# Sheet1.net
KiCad netlist of a schematic drawn in Altium Designer
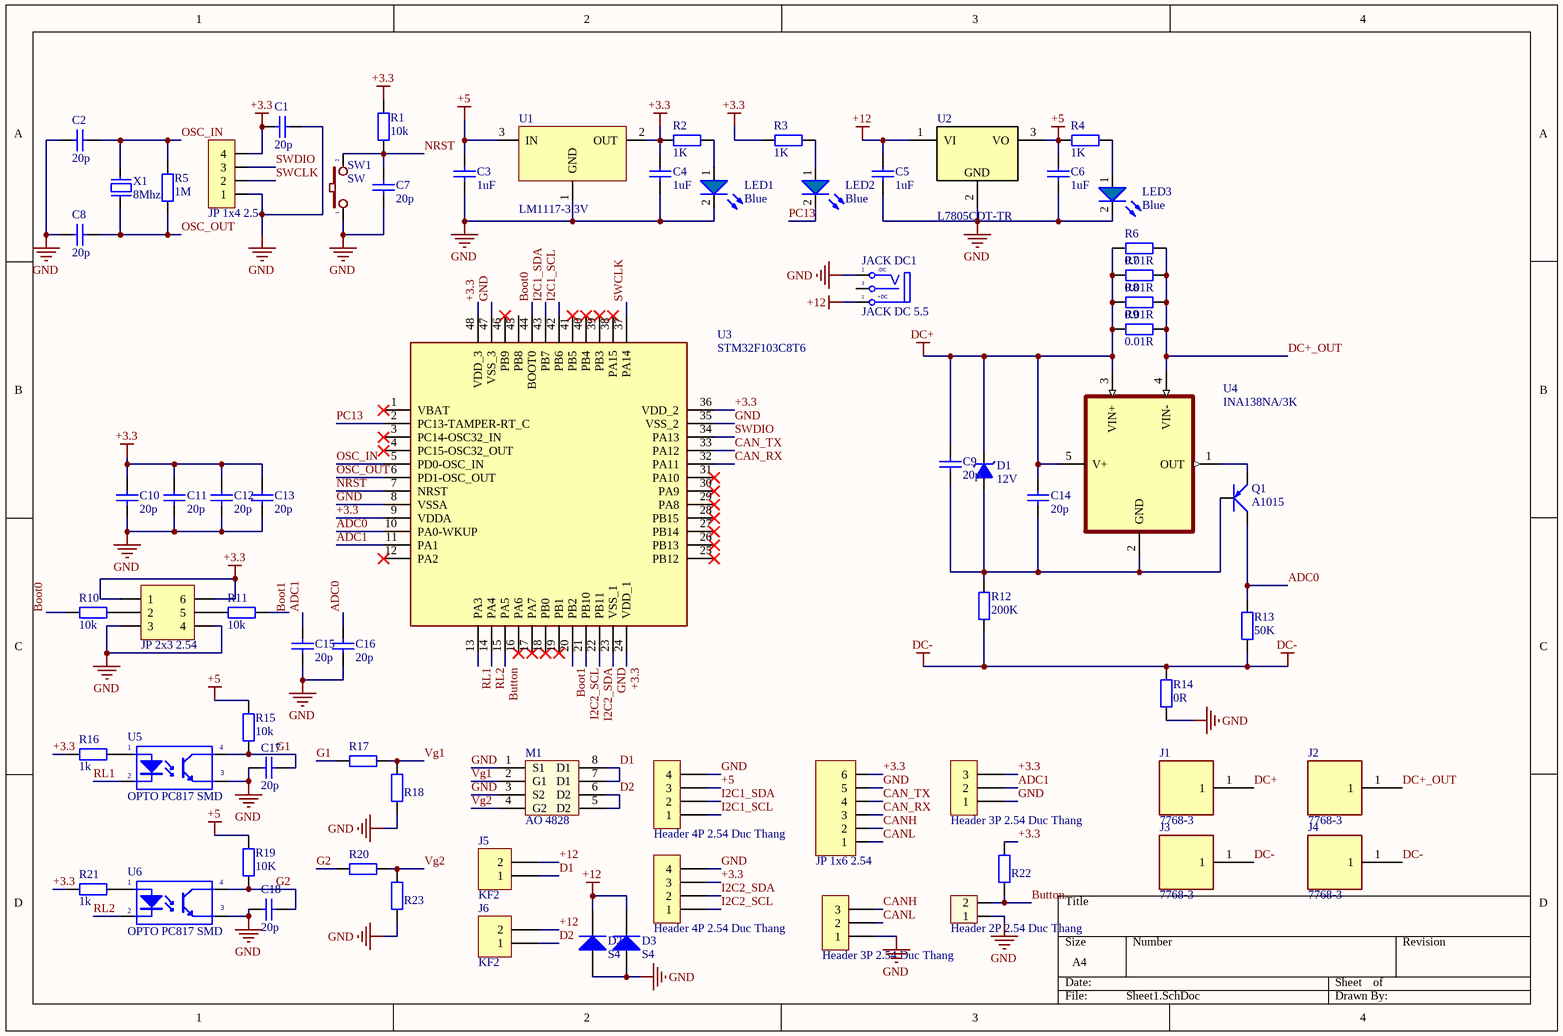
[diagram p0: Sheet1.SchDoc]

(export (version "E")
  (design (tool "Eeschema 10.0.6"))
  (components
    (comp (ref "C1")
      (value "20p")
      (footprint "tu 0805")
      (description "Dán")
      (libsource (lib "Altium_Lib_by_KhueNguyenCreator") (part "Tu 0805 474 50V 10%"))
    )
    (comp (ref "C2")
      (value "20p")
      (footprint "tu 0805")
      (description "Dán")
      (libsource (lib "Altium_Lib_by_KhueNguyenCreator") (part "Tu 0805 474 50V 10%"))
    )
    (comp (ref "C3")
      (value "1uF")
      (footprint "tu 0805")
      (description "Dán")
      (libsource (lib "Altium_Lib_by_KhueNguyenCreator") (part "Tu 0805 474 50V 10%"))
    )
    (comp (ref "C4")
      (value "1uF")
      (footprint "tu 0805")
      (description "Dán")
      (libsource (lib "Altium_Lib_by_KhueNguyenCreator") (part "Tu 0805 474 50V 10%"))
    )
    (comp (ref "C5")
      (value "1uF")
      (footprint "tu 0805")
      (description "Dán")
      (libsource (lib "Altium_Lib_by_KhueNguyenCreator") (part "Tu 0805 474 50V 10%"))
    )
    (comp (ref "C6")
      (value "1uF")
      (footprint "tu 0805")
      (description "Dán")
      (libsource (lib "Altium_Lib_by_KhueNguyenCreator") (part "Tu 0805 474 50V 10%"))
    )
    (comp (ref "C7")
      (value "20p")
      (footprint "tu 0805")
      (description "Dán")
      (libsource (lib "Altium_Lib_by_KhueNguyenCreator") (part "Tu 0805 474 50V 10%"))
    )
    (comp (ref "C8")
      (value "20p")
      (footprint "tu 0805")
      (description "Dán")
      (libsource (lib "Altium_Lib_by_KhueNguyenCreator") (part "Tu 0805 474 50V 10%"))
    )
    (comp (ref "C9")
      (value "20p")
      (footprint "tu 0805")
      (description "Dán")
      (libsource (lib "Altium_Lib_by_KhueNguyenCreator") (part "Tu 0805 474 50V 10%"))
    )
    (comp (ref "C10")
      (value "20p")
      (footprint "tu 0805")
      (description "Dán")
      (libsource (lib "Altium_Lib_by_KhueNguyenCreator") (part "Tu 0805 474 50V 10%"))
    )
    (comp (ref "C11")
      (value "20p")
      (footprint "tu 0805")
      (description "Dán")
      (libsource (lib "Altium_Lib_by_KhueNguyenCreator") (part "Tu 0805 474 50V 10%"))
    )
    (comp (ref "C12")
      (value "20p")
      (footprint "tu 0805")
      (description "Dán")
      (libsource (lib "Altium_Lib_by_KhueNguyenCreator") (part "Tu 0805 474 50V 10%"))
    )
    (comp (ref "C13")
      (value "20p")
      (footprint "tu 0805")
      (description "Dán")
      (libsource (lib "Altium_Lib_by_KhueNguyenCreator") (part "Tu 0805 474 50V 10%"))
    )
    (comp (ref "C14")
      (value "20p")
      (footprint "tu 0805")
      (description "Dán")
      (libsource (lib "Altium_Lib_by_KhueNguyenCreator") (part "Tu 0805 474 50V 10%"))
    )
    (comp (ref "C15")
      (value "20p")
      (footprint "tu 0805")
      (description "Dán")
      (libsource (lib "Altium_Lib_by_KhueNguyenCreator") (part "Tu 0805 474 50V 10%"))
    )
    (comp (ref "C16")
      (value "20p")
      (footprint "tu 0805")
      (description "Dán")
      (libsource (lib "Altium_Lib_by_KhueNguyenCreator") (part "Tu 0805 474 50V 10%"))
    )
    (comp (ref "C17")
      (value "20p")
      (footprint "tu 0805")
      (description "Dán")
      (libsource (lib "Altium_Lib_by_KhueNguyenCreator") (part "Tu 0805 474 50V 10%"))
    )
    (comp (ref "C18")
      (value "20p")
      (footprint "tu 0805")
      (description "Dán")
      (libsource (lib "Altium_Lib_by_KhueNguyenCreator") (part "Tu 0805 474 50V 10%"))
    )
    (comp (ref "D1")
      (value "12V")
      (footprint "DIODE ZENNER SMD SOD80")
      (description "Dán")
      (libsource (lib "Altium_Lib_by_KhueNguyenCreator") (part "Diode Zener 12V"))
    )
    (comp (ref "D2")
      (value "S4")
      (footprint "DIODE SOD-123")
      (description "Dán")
      (libsource (lib "Altium_Lib_by_KhueNguyenCreator") (part "Diode S4"))
    )
    (comp (ref "D3")
      (value "S4")
      (footprint "DIODE SOD-123")
      (description "Dán")
      (libsource (lib "Altium_Lib_by_KhueNguyenCreator") (part "Diode S4"))
    )
    (comp (ref "H1")
      (value "Header 4P 2.54 Duc Thang")
      (footprint "XH2.54M-4")
      (description "Cắm")
      (libsource (lib "Altium_Lib_by_KhueNguyenCreator") (part "Header 4P 2.54 Duc Thang"))
    )
    (comp (ref "H2")
      (value "Header 3P 2.54 Duc Thang")
      (footprint "XH2.54M-3")
      (description "Cắm")
      (libsource (lib "Altium_Lib_by_KhueNguyenCreator") (part "Header 3P 2.54 Duc Thang"))
    )
    (comp (ref "H3")
      (value "Header 4P 2.54 Duc Thang")
      (footprint "XH2.54M-4")
      (description "Cắm")
      (libsource (lib "Altium_Lib_by_KhueNguyenCreator") (part "Header 4P 2.54 Duc Thang"))
    )
    (comp (ref "H4")
      (value "Header 3P 2.54 Duc Thang")
      (footprint "XH2.54M-3")
      (description "Cắm")
      (libsource (lib "Altium_Lib_by_KhueNguyenCreator") (part "Header 3P 2.54 Duc Thang"))
    )
    (comp (ref "H5")
      (value "Header 2P 2.54 Duc Thang")
      (footprint "XH2.54M-2")
      (description "Cắm")
      (libsource (lib "Altium_Lib_by_KhueNguyenCreator") (part "Header 2P 2.54 Duc Thang"))
    )
    (comp (ref "J1")
      (value "7768-3")
      (footprint "KEYSTONE_7768-3")
      (libsource (lib "7768-3") (part "7768-3"))
    )
    (comp (ref "J2")
      (value "7768-3")
      (footprint "KEYSTONE_7768-3")
      (libsource (lib "7768-3") (part "7768-3"))
    )
    (comp (ref "J3")
      (value "7768-3")
      (footprint "KEYSTONE_7768-3")
      (libsource (lib "7768-3") (part "7768-3"))
    )
    (comp (ref "J4")
      (value "7768-3")
      (footprint "KEYSTONE_7768-3")
      (libsource (lib "7768-3") (part "7768-3"))
    )
    (comp (ref "J5")
      (value "KF2")
      (footprint "KF2-5.08")
      (fields
        (field (name "MANUFACTURER") "Würth Elektronik eiSos GmbH")
        (field (name "PARTNO") "691103110002")
        (field (name "CREATED BY") "Karrer Zheng")
      )
      (libsource (lib "TechMT.VN_Lib_Project v2") (part "KF2"))
    )
    (comp (ref "J6")
      (value "KF2")
      (footprint "KF2-5.08")
      (fields
        (field (name "MANUFACTURER") "Würth Elektronik eiSos GmbH")
        (field (name "PARTNO") "691103110002")
        (field (name "CREATED BY") "Karrer Zheng")
      )
      (libsource (lib "TechMT.VN_Lib_Project v2") (part "KF2"))
    )
    (comp (ref "JACK DC1")
      (value "JACK DC 5.5")
      (footprint "JACK DC 5.5")
      (libsource (lib "Altium_Lib_by_KhueNguyenCreator") (part "JACK DC 5.5"))
    )
    (comp (ref "JP1")
      (value "JP 1x4 2.54")
      (footprint "JP 1x4 DT")
      (description "Cắm")
      (libsource (lib "Altium_Lib_by_KhueNguyenCreator") (part "JP 1x4 2.54 Duc Thang"))
    )
    (comp (ref "JP2")
      (value "JP 2x3 2.54")
      (footprint "JP 2x3 DT")
      (description "Cắm")
      (libsource (lib "Altium_Lib_by_KhueNguyenCreator") (part "JP 2x3 2.54 Duc Thang"))
    )
    (comp (ref "JP3")
      (value "JP 1x6 2.54")
      (footprint "JP 1x6 CT")
      (description "Cắm")
      (libsource (lib "Altium_Lib_by_KhueNguyenCreator") (part "JP 1x6 2.54 Cai Thang"))
    )
    (comp (ref "LED1")
      (value "Blue")
      (footprint "LED-0805-Blue")
      (description "LED Blue 10mA 2.2v")
      (fields (field (name "Comment") "LED-Blue"))
      (libsource (lib "TechMT.VN_Lib_Project v2") (part "LED-Blue"))
    )
    (comp (ref "LED2")
      (value "Blue")
      (footprint "LED-0805-Blue")
      (description "LED Blue 10mA 2.2v")
      (fields (field (name "Comment") "LED-Blue"))
      (libsource (lib "TechMT.VN_Lib_Project v2") (part "LED-Blue"))
    )
    (comp (ref "LED3")
      (value "Blue")
      (footprint "LED-0805-Blue")
      (description "LED Blue 10mA 2.2v")
      (fields (field (name "Comment") "LED-Blue"))
      (libsource (lib "TechMT.VN_Lib_Project v2") (part "LED-Blue"))
    )
    (comp (ref "M1")
      (value "AO 4828")
      (footprint "SOp 8")
      (description "Dán")
      (libsource (lib "Altium_Lib_by_KhueNguyenCreator") (part "APM 4828 SMD"))
    )
    (comp (ref "Q1")
      (value "A1015")
      (footprint "TO92")
      (description "PNP 600mW, ECB")
      (libsource (lib "Altium_Lib_by_KhueNguyenCreator") (part "A1015"))
    )
    (comp (ref "R1")
      (value "10k")
      (footprint "tro smd 0805")
      (description "Dán")
      (libsource (lib "Altium_Lib_by_KhueNguyenCreator") (part "Tro 0805 1% 33k"))
    )
    (comp (ref "R2")
      (value "1K")
      (footprint "tro smd 0805")
      (description "Dán")
      (libsource (lib "Altium_Lib_by_KhueNguyenCreator") (part "Tro 0805 1% 33k"))
    )
    (comp (ref "R3")
      (value "1K")
      (footprint "tro smd 0805")
      (description "Dán")
      (libsource (lib "Altium_Lib_by_KhueNguyenCreator") (part "Tro 0805 1% 33k"))
    )
    (comp (ref "R4")
      (value "1K")
      (footprint "tro smd 0805")
      (description "Dán")
      (libsource (lib "Altium_Lib_by_KhueNguyenCreator") (part "Tro 0805 1% 33k"))
    )
    (comp (ref "R5")
      (value "1M")
      (footprint "tro smd 0805")
      (description "Dán")
      (libsource (lib "Altium_Lib_by_KhueNguyenCreator") (part "Tro 0805 1% 33k"))
    )
    (comp (ref "R6")
      (value "0.01R")
      (footprint "tro smd 2512")
      (description "Dán")
      (libsource (lib "Altium_Lib_by_KhueNguyenCreator") (part "Tro 2512 1% 0.01R"))
    )
    (comp (ref "R7")
      (value "0.01R")
      (footprint "tro smd 2512")
      (description "Dán")
      (libsource (lib "Altium_Lib_by_KhueNguyenCreator") (part "Tro 2512 1% 0.01R"))
    )
    (comp (ref "R8")
      (value "0.01R")
      (footprint "tro smd 2512")
      (description "Dán")
      (libsource (lib "Altium_Lib_by_KhueNguyenCreator") (part "Tro 2512 1% 0.01R"))
    )
    (comp (ref "R9")
      (value "0.01R")
      (footprint "tro smd 2512")
      (description "Dán")
      (libsource (lib "Altium_Lib_by_KhueNguyenCreator") (part "Tro 2512 1% 0.01R"))
    )
    (comp (ref "R10")
      (value "10k")
      (footprint "tro smd 0805")
      (description "Dán")
      (libsource (lib "Altium_Lib_by_KhueNguyenCreator") (part "Tro 0805 1% 33k"))
    )
    (comp (ref "R11")
      (value "10k")
      (footprint "tro smd 0805")
      (description "Dán")
      (libsource (lib "Altium_Lib_by_KhueNguyenCreator") (part "Tro 0805 1% 33k"))
    )
    (comp (ref "R12")
      (value "200K")
      (footprint "tro vach 1/4w")
      (description "Cắm")
      (libsource (lib "Altium_Lib_by_KhueNguyenCreator") (part "Tro Vach 1/4W 5% 1.2M"))
    )
    (comp (ref "R13")
      (value "50K")
      (footprint "tro smd 0805")
      (description "Dán")
      (libsource (lib "Altium_Lib_by_KhueNguyenCreator") (part "Tro 0805 1% 33k"))
    )
    (comp (ref "R14")
      (value "0R")
      (footprint "tro smd 0805")
      (description "Dán")
      (libsource (lib "Altium_Lib_by_KhueNguyenCreator") (part "Tro 0805 1% 33k"))
    )
    (comp (ref "R15")
      (value "10k")
      (footprint "tro smd 0805")
      (description "Dán")
      (libsource (lib "Altium_Lib_by_KhueNguyenCreator") (part "Tro 0805 1% 33k"))
    )
    (comp (ref "R16")
      (value "1k")
      (footprint "tro smd 0805")
      (description "Dán")
      (libsource (lib "Altium_Lib_by_KhueNguyenCreator") (part "Tro 0805 1% 33k"))
    )
    (comp (ref "R17")
      (value "1k")
      (footprint "tro smd 0805")
      (description "Dán")
      (libsource (lib "Altium_Lib_by_KhueNguyenCreator") (part "Tro 0805 1% 33k"))
    )
    (comp (ref "R18")
      (value "10k")
      (footprint "tro smd 0805")
      (description "Dán")
      (libsource (lib "Altium_Lib_by_KhueNguyenCreator") (part "Tro 0805 1% 33k"))
    )
    (comp (ref "R19")
      (value "10K")
      (footprint "tro smd 0805")
      (description "Dán")
      (libsource (lib "Altium_Lib_by_KhueNguyenCreator") (part "Tro 0805 1% 33k"))
    )
    (comp (ref "R20")
      (value "1k")
      (footprint "tro smd 0805")
      (description "Dán")
      (libsource (lib "Altium_Lib_by_KhueNguyenCreator") (part "Tro 0805 1% 33k"))
    )
    (comp (ref "R21")
      (value "1k")
      (footprint "tro smd 0805")
      (description "Dán")
      (libsource (lib "Altium_Lib_by_KhueNguyenCreator") (part "Tro 0805 1% 33k"))
    )
    (comp (ref "R22")
      (value "10k")
      (footprint "tro smd 0805")
      (description "Dán")
      (libsource (lib "Altium_Lib_by_KhueNguyenCreator") (part "Tro 0805 1% 33k"))
    )
    (comp (ref "R23")
      (value "10k")
      (footprint "tro smd 0805")
      (description "Dán")
      (libsource (lib "Altium_Lib_by_KhueNguyenCreator") (part "Tro 0805 1% 33k"))
    )
    (comp (ref "SW1")
      (value "SW")
      (footprint "SW1-SMD")
      (description "Switch button 2 pin")
      (libsource (lib "TechMT.VN_Lib_Project v2") (part "SW2"))
    )
    (comp (ref "U1")
      (value "LM1117-3.3V")
      (footprint "SOT223")
      (description "800mA Low-Dropout Linear Regulator")
      (fields (field (name "CREATOR") "Nguyen Ba Bien"))
      (libsource (lib "TechMT.VN_Lib_Project v2") (part "LM1117"))
    )
    (comp (ref "U2")
      (value "L7805CDT-TR")
      (footprint "DPAK_118_446_112X59_SMD")
      (description "Linear Voltage Regulator IC 1 Output 1.5A DPAK")
      (fields (field (name "MANUFACTURER") "Diodes"))
      (libsource (lib "Altium_Lib_by_KhueNguyenCreator") (part "REG_35V_5V-1.5A-7.5W-DPAK"))
    )
    (comp (ref "U3")
      (value "STM32F103C8T6")
      (footprint "LQFP-48_19.6_393_58X11_SMD")
      (description "ARM® Cortex®-M3 STM32F1 Microcontroller IC 32-Bit 72MHz 64KB (64K x 8) FLASH 48-LQFP (7x7)")
      (fields (field (name "MANUFACTURER") "STMicroelectronics"))
      (libsource (lib "Altium_Lib_by_KhueNguyenCreator") (part "IC_STM32F103C8T6"))
    )
    (comp (ref "U4")
      (value "INA138NA/3K")
      (footprint "SOT95P280X145-5N")
      (description "2.7 to 36V, 800kHz Variable gain current sense amplifier 5-SOT-23 -40 to 125")
      (fields (field (name "MF") "Texas Instruments"))
      (libsource (lib "INA138NA_3K") (part "INA138NA/3K"))
    )
    (comp (ref "U5")
      (value "OPTO PC817 SMD")
      (footprint "SOP4")
      (description "Single Opto")
      (libsource (lib "Altium_Lib_by_KhueNguyenCreator") (part "OPTO PC817 SMD"))
    )
    (comp (ref "U6")
      (value "OPTO PC817 SMD")
      (footprint "SOP4")
      (description "Single Opto")
      (libsource (lib "Altium_Lib_by_KhueNguyenCreator") (part "OPTO PC817 SMD"))
    )
    (comp (ref "X1")
      (value "8Mhz")
      (footprint "XT2")
      (description "Crystal, 32.768 KHz, -40 to 85 degC, 3.2 x 1.5 x 0.9 mm SMD")
      (libsource (lib "TechMT.VN_Lib_Project v2") (part "XT2"))
    )
  )
  (nets
    (net (code "1") (name "+3.3") (class "Default")
      (node (ref "C1") (pin "1") (pinfunction "1_1") (pintype "passive"))
      (node (ref "C10") (pin "1") (pinfunction "1_1") (pintype "passive"))
      (node (ref "C11") (pin "1") (pinfunction "1_1") (pintype "passive"))
      (node (ref "C12") (pin "1") (pinfunction "1_1") (pintype "passive"))
      (node (ref "C13") (pin "1") (pinfunction "1_1") (pintype "passive"))
      (node (ref "C4") (pin "1") (pinfunction "1_1") (pintype "passive"))
      (node (ref "H2") (pin "3") (pinfunction "3_3") (pintype "passive"))
      (node (ref "H3") (pin "3") (pinfunction "3_3") (pintype "passive"))
      (node (ref "JP1") (pin "4") (pinfunction "4_4") (pintype "passive"))
      (node (ref "JP2") (pin "1") (pinfunction "1_1") (pintype "passive"))
      (node (ref "JP2") (pin "6") (pinfunction "6_6") (pintype "passive"))
      (node (ref "JP3") (pin "6") (pinfunction "6_6") (pintype "passive"))
      (node (ref "R1") (pin "2") (pinfunction "2_2") (pintype "passive"))
      (node (ref "R16") (pin "1") (pinfunction "1_1") (pintype "passive"))
      (node (ref "R2") (pin "2") (pinfunction "2_2") (pintype "passive"))
      (node (ref "R21") (pin "1") (pinfunction "1_1") (pintype "passive"))
      (node (ref "R22") (pin "2") (pinfunction "2_2") (pintype "passive"))
      (node (ref "R3") (pin "2") (pinfunction "2_2") (pintype "passive"))
      (node (ref "U1") (pin "2") (pinfunction "OUT_2") (pintype "passive"))
      (node (ref "U3") (pin "24") (pinfunction "VDD_1_24") (pintype "passive"))
      (node (ref "U3") (pin "36") (pinfunction "VDD_2_36") (pintype "passive"))
      (node (ref "U3") (pin "48") (pinfunction "VDD_3_48") (pintype "passive"))
      (node (ref "U3") (pin "9") (pinfunction "VDDA_9") (pintype "passive"))
    )
    (net (code "2") (name "+5") (class "Default")
      (node (ref "C3") (pin "1") (pinfunction "1_1") (pintype "passive"))
      (node (ref "C6") (pin "1") (pinfunction "1_1") (pintype "passive"))
      (node (ref "H1") (pin "3") (pinfunction "3_3") (pintype "passive"))
      (node (ref "R15") (pin "1") (pinfunction "1_1") (pintype "passive"))
      (node (ref "R19") (pin "1") (pinfunction "1_1") (pintype "passive"))
      (node (ref "R4") (pin "2") (pinfunction "2_2") (pintype "passive"))
      (node (ref "U1") (pin "3") (pinfunction "IN_3") (pintype "passive"))
      (node (ref "U2") (pin "3") (pinfunction "VO_3") (pintype "passive"))
    )
    (net (code "3") (name "+12") (class "Default")
      (node (ref "C5") (pin "1") (pinfunction "1_1") (pintype "passive"))
      (node (ref "D2") (pin "2") (pinfunction "K_2") (pintype "passive"))
      (node (ref "D3") (pin "2") (pinfunction "K_2") (pintype "passive"))
      (node (ref "J5") (pin "2") (pinfunction "2_2") (pintype "passive"))
      (node (ref "J6") (pin "2") (pinfunction "2_2") (pintype "passive"))
      (node (ref "JACK DC1") (pin "1") (pinfunction "T_1") (pintype "passive"))
      (node (ref "U2") (pin "1") (pinfunction "VI_1") (pintype "passive"))
    )
    (net (code "4") (name "/ADC0") (class "Default")
      (node (ref "C16") (pin "2") (pinfunction "2_2") (pintype "passive"))
      (node (ref "Q1") (pin "2") (pinfunction "C_2") (pintype "passive"))
      (node (ref "R13") (pin "2") (pinfunction "2_2") (pintype "passive"))
      (node (ref "U3") (pin "10") (pinfunction "PA0-WKUP_10") (pintype "passive"))
    )
    (net (code "5") (name "/ADC1") (class "Default")
      (node (ref "C15") (pin "1") (pinfunction "1_1") (pintype "passive"))
      (node (ref "H2") (pin "2") (pinfunction "2_2") (pintype "passive"))
      (node (ref "U3") (pin "11") (pinfunction "PA1_11") (pintype "passive"))
    )
    (net (code "6") (name "/Boot0") (class "Default")
      (node (ref "R10") (pin "1") (pinfunction "1_1") (pintype "passive"))
      (node (ref "U3") (pin "44") (pinfunction "BOOT0_44") (pintype "passive"))
    )
    (net (code "7") (name "/Boot1") (class "Default")
      (node (ref "R11") (pin "2") (pinfunction "2_2") (pintype "passive"))
      (node (ref "U3") (pin "20") (pinfunction "PB2_20") (pintype "passive"))
    )
    (net (code "8") (name "/Button") (class "Default")
      (node (ref "H5") (pin "2") (pinfunction "2_2") (pintype "passive"))
      (node (ref "R22") (pin "1") (pinfunction "1_1") (pintype "passive"))
      (node (ref "U3") (pin "15") (pinfunction "PA5_15") (pintype "passive"))
    )
    (net (code "9") (name "/CANH") (class "Default")
      (node (ref "H4") (pin "3") (pinfunction "3_3") (pintype "passive"))
      (node (ref "JP3") (pin "2") (pinfunction "2_2") (pintype "passive"))
    )
    (net (code "10") (name "/CANL") (class "Default")
      (node (ref "H4") (pin "2") (pinfunction "2_2") (pintype "passive"))
      (node (ref "JP3") (pin "1") (pinfunction "1_1") (pintype "passive"))
    )
    (net (code "11") (name "/CAN_RX") (class "Default")
      (node (ref "JP3") (pin "3") (pinfunction "3_3") (pintype "passive"))
      (node (ref "U3") (pin "32") (pinfunction "PA11_32") (pintype "passive"))
    )
    (net (code "12") (name "/CAN_TX") (class "Default")
      (node (ref "JP3") (pin "4") (pinfunction "4_4") (pintype "passive"))
      (node (ref "U3") (pin "33") (pinfunction "PA12_33") (pintype "passive"))
    )
    (net (code "13") (name "/D1") (class "Default")
      (node (ref "J5") (pin "1") (pinfunction "1_1") (pintype "passive"))
      (node (ref "M1") (pin "7") (pinfunction "D1_7") (pintype "passive"))
      (node (ref "M1") (pin "8") (pinfunction "D1_8") (pintype "passive"))
    )
    (net (code "14") (name "/D2") (class "Default")
      (node (ref "J6") (pin "1") (pinfunction "1_1") (pintype "passive"))
      (node (ref "M1") (pin "5") (pinfunction "D2_5") (pintype "passive"))
      (node (ref "M1") (pin "6") (pinfunction "D2_6") (pintype "passive"))
    )
    (net (code "15") (name "/DC+_OUT") (class "Default")
      (node (ref "J2") (pin "1") (pinfunction "1_1") (pintype "passive"))
      (node (ref "R6") (pin "2") (pinfunction "2_2") (pintype "passive"))
      (node (ref "R7") (pin "2") (pinfunction "2_2") (pintype "passive"))
      (node (ref "R8") (pin "2") (pinfunction "2_2") (pintype "passive"))
      (node (ref "R9") (pin "2") (pinfunction "2_2") (pintype "passive"))
      (node (ref "U4") (pin "4") (pinfunction "VIN-_4") (pintype "input"))
    )
    (net (code "16") (name "/G1") (class "Default")
      (node (ref "C17") (pin "2") (pinfunction "2_2") (pintype "passive"))
      (node (ref "R15") (pin "2") (pinfunction "2_2") (pintype "passive"))
      (node (ref "R17") (pin "1") (pinfunction "1_1") (pintype "passive"))
      (node (ref "U5") (pin "4") (pinfunction "C_4") (pintype "passive"))
    )
    (net (code "17") (name "/G2") (class "Default")
      (node (ref "C18") (pin "2") (pinfunction "2_2") (pintype "passive"))
      (node (ref "R19") (pin "2") (pinfunction "2_2") (pintype "passive"))
      (node (ref "R20") (pin "1") (pinfunction "1_1") (pintype "passive"))
      (node (ref "U6") (pin "4") (pinfunction "C_4") (pintype "passive"))
    )
    (net (code "18") (name "/I2C1_SCL") (class "Default")
      (node (ref "H1") (pin "1") (pinfunction "1_1") (pintype "passive"))
      (node (ref "U3") (pin "42") (pinfunction "PB6_42") (pintype "passive"))
    )
    (net (code "19") (name "/I2C1_SDA") (class "Default")
      (node (ref "H1") (pin "2") (pinfunction "2_2") (pintype "passive"))
      (node (ref "U3") (pin "43") (pinfunction "PB7_43") (pintype "passive"))
    )
    (net (code "20") (name "/I2C2_SCL") (class "Default")
      (node (ref "H3") (pin "1") (pinfunction "1_1") (pintype "passive"))
      (node (ref "U3") (pin "21") (pinfunction "PB10_21") (pintype "passive"))
    )
    (net (code "21") (name "/I2C2_SDA") (class "Default")
      (node (ref "H3") (pin "2") (pinfunction "2_2") (pintype "passive"))
      (node (ref "U3") (pin "22") (pinfunction "PB11_22") (pintype "passive"))
    )
    (net (code "22") (name "/NRST") (class "Default")
      (node (ref "C7") (pin "1") (pinfunction "1_1") (pintype "passive"))
      (node (ref "R1") (pin "1") (pinfunction "1_1") (pintype "passive"))
      (node (ref "SW1") (pin "2") (pinfunction "2_2") (pintype "passive"))
      (node (ref "U3") (pin "7") (pinfunction "NRST_7") (pintype "passive"))
    )
    (net (code "23") (name "/OSC_IN") (class "Default")
      (node (ref "C2") (pin "1") (pinfunction "1_1") (pintype "passive"))
      (node (ref "R5") (pin "1") (pinfunction "1_1") (pintype "passive"))
      (node (ref "U3") (pin "5") (pinfunction "PD0-OSC_IN_5") (pintype "passive"))
      (node (ref "X1") (pin "2") (pinfunction "2_2") (pintype "passive"))
    )
    (net (code "24") (name "/OSC_OUT") (class "Default")
      (node (ref "C8") (pin "1") (pinfunction "1_1") (pintype "passive"))
      (node (ref "R5") (pin "2") (pinfunction "2_2") (pintype "passive"))
      (node (ref "U3") (pin "6") (pinfunction "PD1-OSC_OUT_6") (pintype "passive"))
      (node (ref "X1") (pin "1") (pinfunction "1_1") (pintype "passive"))
    )
    (net (code "25") (name "/PC13") (class "Default")
      (node (ref "LED2") (pin "2") (pinfunction "K_2") (pintype "passive"))
      (node (ref "U3") (pin "2") (pinfunction "PC13-TAMPER-RT_C_2") (pintype "passive"))
    )
    (net (code "26") (name "/RL1") (class "Default")
      (node (ref "U3") (pin "13") (pinfunction "PA3_13") (pintype "passive"))
      (node (ref "U5") (pin "2") (pinfunction "K_2") (pintype "passive"))
    )
    (net (code "27") (name "/RL2") (class "Default")
      (node (ref "U3") (pin "14") (pinfunction "PA4_14") (pintype "passive"))
      (node (ref "U6") (pin "2") (pinfunction "K_2") (pintype "passive"))
    )
    (net (code "28") (name "/SWCLK") (class "Default")
      (node (ref "JP1") (pin "2") (pinfunction "2_2") (pintype "passive"))
      (node (ref "U3") (pin "37") (pinfunction "PA14_37") (pintype "passive"))
    )
    (net (code "29") (name "/SWDIO") (class "Default")
      (node (ref "JP1") (pin "3") (pinfunction "3_3") (pintype "passive"))
      (node (ref "U3") (pin "34") (pinfunction "PA13_34") (pintype "passive"))
    )
    (net (code "30") (name "/Vg1") (class "Default")
      (node (ref "M1") (pin "2") (pinfunction "G1_2") (pintype "passive"))
      (node (ref "R17") (pin "2") (pinfunction "2_2") (pintype "passive"))
      (node (ref "R18") (pin "2") (pinfunction "2_2") (pintype "passive"))
    )
    (net (code "31") (name "/Vg2") (class "Default")
      (node (ref "M1") (pin "4") (pinfunction "G2_4") (pintype "passive"))
      (node (ref "R20") (pin "2") (pinfunction "2_2") (pintype "passive"))
      (node (ref "R23") (pin "2") (pinfunction "2_2") (pintype "passive"))
    )
    (net (code "32") (name "DC+") (class "Default")
      (node (ref "C14") (pin "1") (pinfunction "1_1") (pintype "passive"))
      (node (ref "C9") (pin "1") (pinfunction "1_1") (pintype "passive"))
      (node (ref "D1") (pin "2") (pinfunction "K_2") (pintype "passive"))
      (node (ref "J1") (pin "1") (pinfunction "1_1") (pintype "passive"))
      (node (ref "R6") (pin "1") (pinfunction "1_1") (pintype "passive"))
      (node (ref "R7") (pin "1") (pinfunction "1_1") (pintype "passive"))
      (node (ref "R8") (pin "1") (pinfunction "1_1") (pintype "passive"))
      (node (ref "R9") (pin "1") (pinfunction "1_1") (pintype "passive"))
      (node (ref "U4") (pin "3") (pinfunction "VIN+_3") (pintype "input"))
      (node (ref "U4") (pin "5") (pinfunction "V+_5") (pintype "power_in"))
    )
    (net (code "33") (name "DC-") (class "Default")
      (node (ref "J3") (pin "1") (pinfunction "1_1") (pintype "passive"))
      (node (ref "J4") (pin "1") (pinfunction "1_1") (pintype "passive"))
      (node (ref "R12") (pin "1") (pinfunction "1_1") (pintype "passive"))
      (node (ref "R13") (pin "1") (pinfunction "1_1") (pintype "passive"))
      (node (ref "R14") (pin "2") (pinfunction "2_2") (pintype "passive"))
    )
    (net (code "34") (name "GND") (class "Default")
      (node (ref "C1") (pin "2") (pinfunction "2_2") (pintype "passive"))
      (node (ref "C10") (pin "2") (pinfunction "2_2") (pintype "passive"))
      (node (ref "C11") (pin "2") (pinfunction "2_2") (pintype "passive"))
      (node (ref "C12") (pin "2") (pinfunction "2_2") (pintype "passive"))
      (node (ref "C13") (pin "2") (pinfunction "2_2") (pintype "passive"))
      (node (ref "C15") (pin "2") (pinfunction "2_2") (pintype "passive"))
      (node (ref "C16") (pin "1") (pinfunction "1_1") (pintype "passive"))
      (node (ref "C17") (pin "1") (pinfunction "1_1") (pintype "passive"))
      (node (ref "C18") (pin "1") (pinfunction "1_1") (pintype "passive"))
      (node (ref "C2") (pin "2") (pinfunction "2_2") (pintype "passive"))
      (node (ref "C3") (pin "2") (pinfunction "2_2") (pintype "passive"))
      (node (ref "C4") (pin "2") (pinfunction "2_2") (pintype "passive"))
      (node (ref "C5") (pin "2") (pinfunction "2_2") (pintype "passive"))
      (node (ref "C6") (pin "2") (pinfunction "2_2") (pintype "passive"))
      (node (ref "C7") (pin "2") (pinfunction "2_2") (pintype "passive"))
      (node (ref "C8") (pin "2") (pinfunction "2_2") (pintype "passive"))
      (node (ref "D2") (pin "1") (pinfunction "A_1") (pintype "passive"))
      (node (ref "D3") (pin "1") (pinfunction "A_1") (pintype "passive"))
      (node (ref "H1") (pin "4") (pinfunction "4_4") (pintype "passive"))
      (node (ref "H2") (pin "1") (pinfunction "1_1") (pintype "passive"))
      (node (ref "H3") (pin "4") (pinfunction "4_4") (pintype "passive"))
      (node (ref "H4") (pin "1") (pinfunction "1_1") (pintype "passive"))
      (node (ref "H5") (pin "1") (pinfunction "1_1") (pintype "passive"))
      (node (ref "JACK DC1") (pin "2") (pinfunction "TN_2") (pintype "passive"))
      (node (ref "JP1") (pin "1") (pinfunction "1_1") (pintype "passive"))
      (node (ref "JP2") (pin "3") (pinfunction "3_3") (pintype "passive"))
      (node (ref "JP2") (pin "4") (pinfunction "4_4") (pintype "passive"))
      (node (ref "JP3") (pin "5") (pinfunction "5_5") (pintype "passive"))
      (node (ref "LED1") (pin "2") (pinfunction "K_2") (pintype "passive"))
      (node (ref "LED3") (pin "2") (pinfunction "K_2") (pintype "passive"))
      (node (ref "M1") (pin "1") (pinfunction "S1_1") (pintype "passive"))
      (node (ref "M1") (pin "3") (pinfunction "S2_3") (pintype "passive"))
      (node (ref "R14") (pin "1") (pinfunction "1_1") (pintype "passive"))
      (node (ref "R18") (pin "1") (pinfunction "1_1") (pintype "passive"))
      (node (ref "R23") (pin "1") (pinfunction "1_1") (pintype "passive"))
      (node (ref "SW1") (pin "1") (pinfunction "1_1") (pintype "passive"))
      (node (ref "U1") (pin "1") (pinfunction "GND_1") (pintype "passive"))
      (node (ref "U2") (pin "2") (pintype "passive"))
      (node (ref "U3") (pin "23") (pinfunction "VSS_1_23") (pintype "passive"))
      (node (ref "U3") (pin "35") (pinfunction "VSS_2_35") (pintype "passive"))
      (node (ref "U3") (pin "47") (pinfunction "VSS_3_47") (pintype "passive"))
      (node (ref "U3") (pin "8") (pinfunction "VSSA_8") (pintype "passive"))
      (node (ref "U5") (pin "3") (pinfunction "E_3") (pintype "passive"))
      (node (ref "U6") (pin "3") (pinfunction "E_3") (pintype "passive"))
    )
    (net (code "35") (name "Net-(D1-A)") (class "Default")
      (node (ref "C14") (pin "2") (pinfunction "2_2") (pintype "passive"))
      (node (ref "C9") (pin "2") (pinfunction "2_2") (pintype "passive"))
      (node (ref "D1") (pin "1") (pinfunction "A_1") (pintype "passive"))
      (node (ref "Q1") (pin "3") (pinfunction "B_3") (pintype "passive"))
      (node (ref "R12") (pin "2") (pinfunction "2_2") (pintype "passive"))
      (node (ref "U4") (pin "2") (pinfunction "GND_2") (pintype "power_in"))
    )
    (net (code "36") (name "Net-(JP2-Pad2)") (class "Default")
      (node (ref "JP2") (pin "2") (pinfunction "2_2") (pintype "passive"))
      (node (ref "R10") (pin "2") (pinfunction "2_2") (pintype "passive"))
    )
    (net (code "37") (name "Net-(JP2-Pad5)") (class "Default")
      (node (ref "JP2") (pin "5") (pinfunction "5_5") (pintype "passive"))
      (node (ref "R11") (pin "1") (pinfunction "1_1") (pintype "passive"))
    )
    (net (code "38") (name "Net-(LED1-A)") (class "Default")
      (node (ref "LED1") (pin "1") (pinfunction "A_1") (pintype "passive"))
      (node (ref "R2") (pin "1") (pinfunction "1_1") (pintype "passive"))
    )
    (net (code "39") (name "Net-(LED2-A)") (class "Default")
      (node (ref "LED2") (pin "1") (pinfunction "A_1") (pintype "passive"))
      (node (ref "R3") (pin "1") (pinfunction "1_1") (pintype "passive"))
    )
    (net (code "40") (name "Net-(LED3-A)") (class "Default")
      (node (ref "LED3") (pin "1") (pinfunction "A_1") (pintype "passive"))
      (node (ref "R4") (pin "1") (pinfunction "1_1") (pintype "passive"))
    )
    (net (code "41") (name "Net-(Q1-E)") (class "Default")
      (node (ref "Q1") (pin "1") (pinfunction "E_1") (pintype "passive"))
      (node (ref "U4") (pin "1") (pinfunction "OUT_1") (pintype "output"))
    )
    (net (code "42") (name "Net-(U5-A)") (class "Default")
      (node (ref "R16") (pin "2") (pinfunction "2_2") (pintype "passive"))
      (node (ref "U5") (pin "1") (pinfunction "A_1") (pintype "passive"))
    )
    (net (code "43") (name "Net-(U6-A)") (class "Default")
      (node (ref "R21") (pin "2") (pinfunction "2_2") (pintype "passive"))
      (node (ref "U6") (pin "1") (pinfunction "A_1") (pintype "passive"))
    )
    (net (code "44") (name "unconnected-(JACK DC1-S-Pad3)") (class "Default")
      (node (ref "JACK DC1") (pin "3") (pinfunction "S_3") (pintype "power_in"))
    )
    (net (code "45") (name "unconnected-(U3-PA2-Pad12)") (class "Default")
      (node (ref "U3") (pin "12") (pinfunction "PA2_12") (pintype "passive+no_connect"))
    )
    (net (code "46") (name "unconnected-(U3-PA6-Pad16)") (class "Default")
      (node (ref "U3") (pin "16") (pinfunction "PA6_16") (pintype "passive+no_connect"))
    )
    (net (code "47") (name "unconnected-(U3-PA7-Pad17)") (class "Default")
      (node (ref "U3") (pin "17") (pinfunction "PA7_17") (pintype "passive+no_connect"))
    )
    (net (code "48") (name "unconnected-(U3-PA8-Pad29)") (class "Default")
      (node (ref "U3") (pin "29") (pinfunction "PA8_29") (pintype "passive+no_connect"))
    )
    (net (code "49") (name "unconnected-(U3-PA9-Pad30)") (class "Default")
      (node (ref "U3") (pin "30") (pinfunction "PA9_30") (pintype "passive+no_connect"))
    )
    (net (code "50") (name "unconnected-(U3-PA10-Pad31)") (class "Default")
      (node (ref "U3") (pin "31") (pinfunction "PA10_31") (pintype "passive+no_connect"))
    )
    (net (code "51") (name "unconnected-(U3-PA15-Pad38)") (class "Default")
      (node (ref "U3") (pin "38") (pinfunction "PA15_38") (pintype "passive+no_connect"))
    )
    (net (code "52") (name "unconnected-(U3-PB0-Pad18)") (class "Default")
      (node (ref "U3") (pin "18") (pinfunction "PB0_18") (pintype "passive+no_connect"))
    )
    (net (code "53") (name "unconnected-(U3-PB1-Pad19)") (class "Default")
      (node (ref "U3") (pin "19") (pinfunction "PB1_19") (pintype "passive+no_connect"))
    )
    (net (code "54") (name "unconnected-(U3-PB3-Pad39)") (class "Default")
      (node (ref "U3") (pin "39") (pinfunction "PB3_39") (pintype "passive+no_connect"))
    )
    (net (code "55") (name "unconnected-(U3-PB4-Pad40)") (class "Default")
      (node (ref "U3") (pin "40") (pinfunction "PB4_40") (pintype "passive+no_connect"))
    )
    (net (code "56") (name "unconnected-(U3-PB5-Pad41)") (class "Default")
      (node (ref "U3") (pin "41") (pinfunction "PB5_41") (pintype "passive+no_connect"))
    )
    (net (code "57") (name "unconnected-(U3-PB8-Pad45)") (class "Default")
      (node (ref "U3") (pin "45") (pinfunction "PB8_45") (pintype "passive"))
    )
    (net (code "58") (name "unconnected-(U3-PB9-Pad46)") (class "Default")
      (node (ref "U3") (pin "46") (pinfunction "PB9_46") (pintype "passive+no_connect"))
    )
    (net (code "59") (name "unconnected-(U3-PB12-Pad25)") (class "Default")
      (node (ref "U3") (pin "25") (pinfunction "PB12_25") (pintype "passive+no_connect"))
    )
    (net (code "60") (name "unconnected-(U3-PB13-Pad26)") (class "Default")
      (node (ref "U3") (pin "26") (pinfunction "PB13_26") (pintype "passive+no_connect"))
    )
    (net (code "61") (name "unconnected-(U3-PB14-Pad27)") (class "Default")
      (node (ref "U3") (pin "27") (pinfunction "PB14_27") (pintype "passive+no_connect"))
    )
    (net (code "62") (name "unconnected-(U3-PB15-Pad28)") (class "Default")
      (node (ref "U3") (pin "28") (pinfunction "PB15_28") (pintype "passive+no_connect"))
    )
    (net (code "63") (name "unconnected-(U3-PC14-OSC32_IN-Pad3)") (class "Default")
      (node (ref "U3") (pin "3") (pinfunction "PC14-OSC32_IN_3") (pintype "passive+no_connect"))
    )
    (net (code "64") (name "unconnected-(U3-PC15-OSC32_OUT-Pad4)") (class "Default")
      (node (ref "U3") (pin "4") (pinfunction "PC15-OSC32_OUT_4") (pintype "passive+no_connect"))
    )
    (net (code "65") (name "unconnected-(U3-VBAT-Pad1)") (class "Default")
      (node (ref "U3") (pin "1") (pinfunction "VBAT_1") (pintype "passive+no_connect"))
    )
  )
)
